# F7.net
KiCad netlist of a schematic drawn in EAGLE
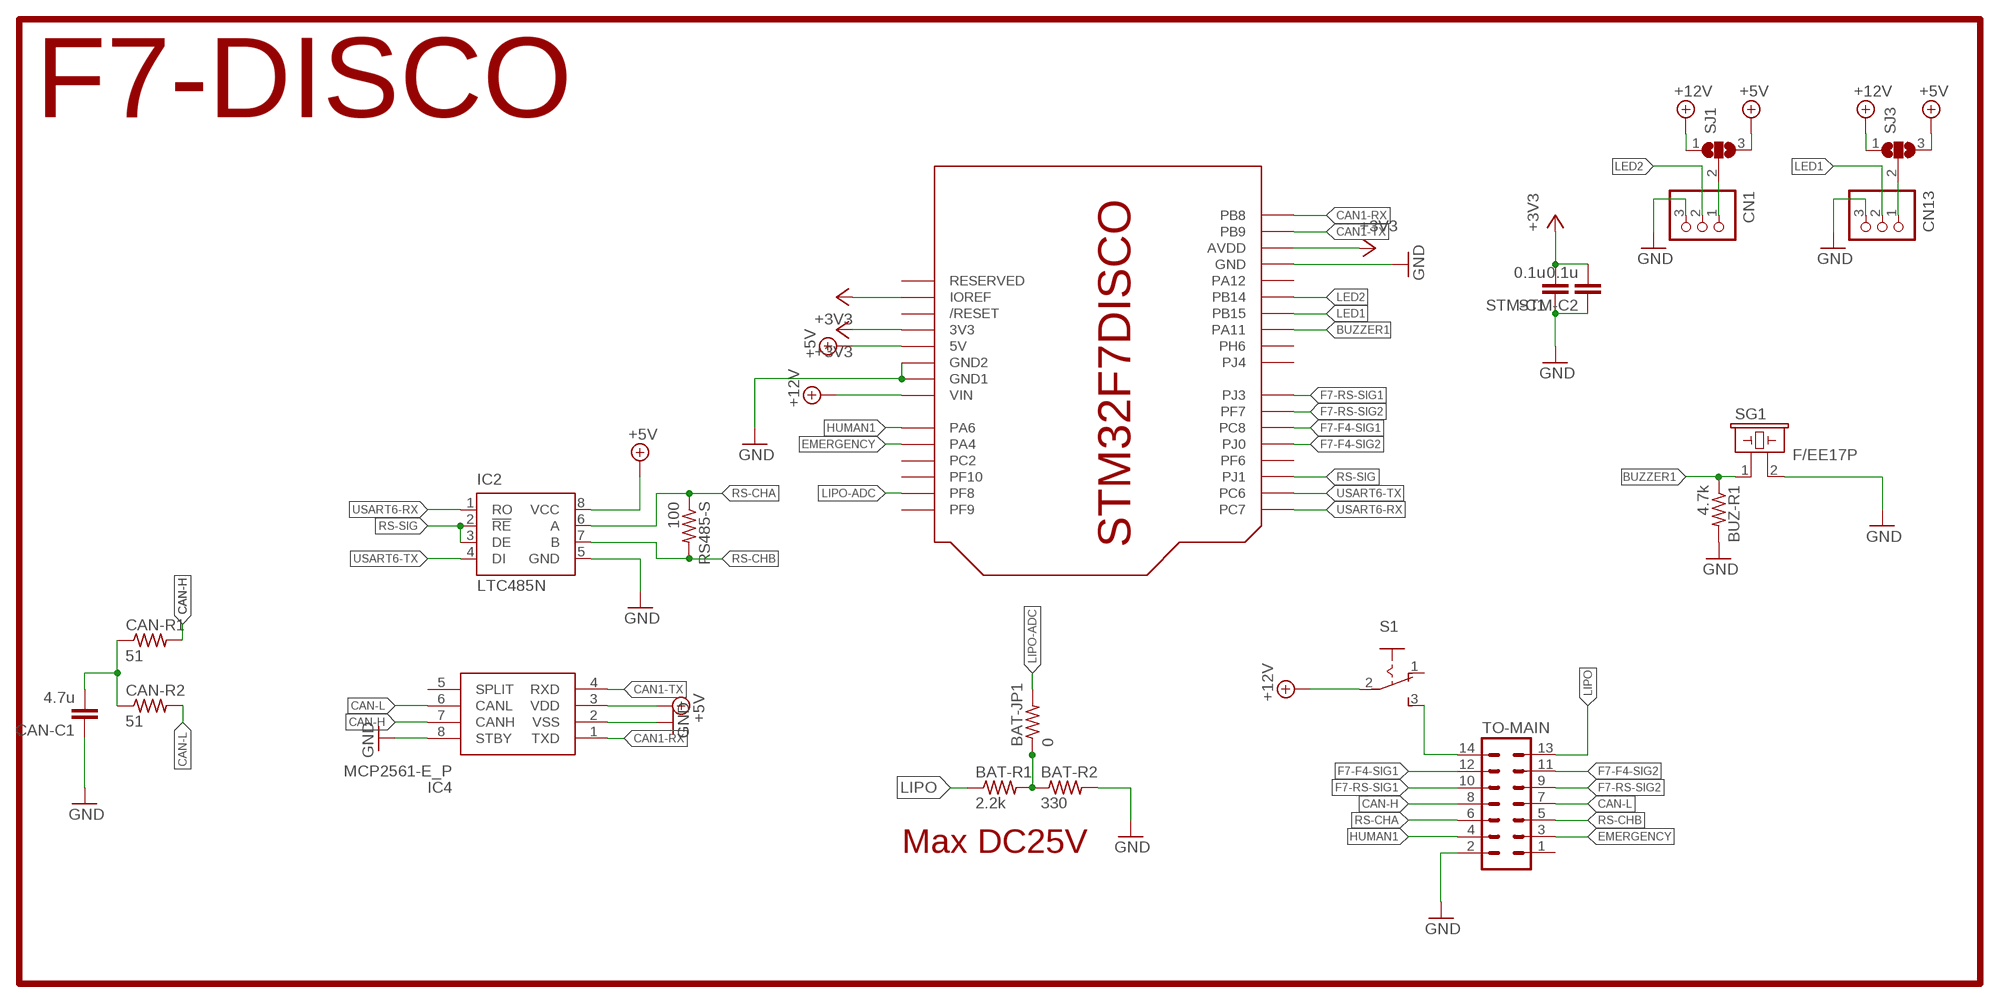
[diagram p0: schematic, sheet 1]

(export (version "E")
  (design (tool "Eeschema 10.0.6"))
  (components
    (comp (ref "BAT-JP1")
      (value "0")
      (footprint "eagle-import:R0805")
      (libsource (lib "eagle-import") (part "R-US_R0805"))
    )
    (comp (ref "BAT-R1")
      (value "2.2k")
      (footprint "eagle-import:R0805")
      (libsource (lib "eagle-import") (part "R-US_R0805"))
    )
    (comp (ref "BAT-R2")
      (value "330")
      (footprint "eagle-import:R0805")
      (libsource (lib "eagle-import") (part "R-US_R0805"))
    )
    (comp (ref "BUZ-R1")
      (value "4.7k")
      (footprint "eagle-import:R0805")
      (libsource (lib "eagle-import") (part "R-US_R0805"))
    )
    (comp (ref "CAN-C1")
      (value "4.7u")
      (footprint "eagle-import:C0805")
      (libsource (lib "eagle-import") (part "C-EUC0805"))
    )
    (comp (ref "CAN-R1")
      (value "51")
      (footprint "eagle-import:R0805")
      (libsource (lib "eagle-import") (part "R-US_R0805"))
    )
    (comp (ref "CAN-R2")
      (value "51")
      (footprint "eagle-import:R0805")
      (libsource (lib "eagle-import") (part "R-US_R0805"))
    )
    (comp (ref "CN1")
      (value "B3P-VH")
      (footprint "eagle-import:B3P-VH")
      (libsource (lib "eagle-import") (part "B3P-VH"))
    )
    (comp (ref "CN13")
      (value "B3P-VH")
      (footprint "eagle-import:B3P-VH")
      (libsource (lib "eagle-import") (part "B3P-VH"))
    )
    (comp (ref "IC2")
      (value "LTC485N")
      (footprint "eagle-import:DIL08")
      (libsource (lib "eagle-import") (part "LTC485N"))
    )
    (comp (ref "IC4")
      (value "MCP2561-E_P")
      (footprint "eagle-import:DIP781W56P254L950H533Q8N")
      (fields
        (field (name "MANUFACTURER_PART_NUMBER") "MCP2561-E/P")
        (field (name "MOUSER_PART_NUMBER") "579-MCP2561-E/P")
        (field (name "RS_PART_NUMBER") "1652124")
      )
      (libsource (lib "eagle-import") (part "MCP2561-E_P"))
    )
    (comp (ref "RS485-S")
      (value "100")
      (footprint "eagle-import:R0805")
      (libsource (lib "eagle-import") (part "R-US_R0805"))
    )
    (comp (ref "S1")
      (value "255SB")
      (footprint "eagle-import:255SB")
      (libsource (lib "eagle-import") (part "255SB"))
    )
    (comp (ref "SG1")
      (value "F/EE17P")
      (footprint "eagle-import:F_EE17P")
      (libsource (lib "eagle-import") (part "F/EE17P"))
    )
    (comp (ref "SJ1")
      (value "SJ2WW")
      (footprint "eagle-import:SJ_2W")
      (libsource (lib "eagle-import") (part "SJ2WW"))
    )
    (comp (ref "SJ3")
      (value "SJ2WW")
      (footprint "eagle-import:SJ_2W")
      (libsource (lib "eagle-import") (part "SJ2WW"))
    )
    (comp (ref "STM-C1")
      (value "0.1u")
      (footprint "eagle-import:C0805")
      (libsource (lib "eagle-import") (part "C-EUC0805"))
    )
    (comp (ref "STM-C2")
      (value "0.1u")
      (footprint "eagle-import:C0805")
      (libsource (lib "eagle-import") (part "C-EUC0805"))
    )
    (comp (ref "TO-MAIN")
      (value "ML14")
      (footprint "eagle-import:ML14")
      (libsource (lib "eagle-import") (part "ML14"))
    )
    (comp (ref "U$1")
      (value "F7-DISCO-ARDUINO")
      (footprint "eagle-import:F7-DISCO-ARDUINO")
      (libsource (lib "eagle-import") (part "F7-DISCO-ARDUINO"))
    )
  )
  (nets
    (net (code "1") (name "+5V") (class "Default")
      (node (ref "IC2") (pin "8") (pinfunction "VCC_8") (pintype "input"))
      (node (ref "IC4") (pin "3") (pinfunction "VDD_3") (pintype "bidirectional"))
      (node (ref "SJ1") (pin "3") (pinfunction "3_3") (pintype "passive"))
      (node (ref "SJ3") (pin "3") (pinfunction "3_3") (pintype "passive"))
      (node (ref "U$1") (pin "5V") (pinfunction "5V_5V") (pintype "power_in"))
    )
    (net (code "2") (name "+9V") (class "Default")
      (node (ref "S1") (pin "2") (pinfunction "P_2") (pintype "passive"))
      (node (ref "SJ1") (pin "1") (pinfunction "1_1") (pintype "passive"))
      (node (ref "SJ3") (pin "1") (pinfunction "1_1") (pintype "passive"))
      (node (ref "U$1") (pin "VIN") (pinfunction "VIN_VIN") (pintype "power_in"))
    )
    (net (code "3") (name "BUZZER1") (class "Default")
      (node (ref "BUZ-R1") (pin "1") (pinfunction "1_1") (pintype "passive"))
      (node (ref "SG1") (pin "1") (pinfunction "1_1") (pintype "passive"))
      (node (ref "U$1") (pin "PA11") (pinfunction "PA11_PA11") (pintype "bidirectional"))
    )
    (net (code "4") (name "CAN-H") (class "Default")
      (node (ref "CAN-R1") (pin "2") (pinfunction "2_2") (pintype "passive"))
      (node (ref "IC4") (pin "7") (pinfunction "CANH_7") (pintype "bidirectional"))
      (node (ref "TO-MAIN") (pin "8") (pinfunction "8_8") (pintype "passive"))
    )
    (net (code "5") (name "CAN-L") (class "Default")
      (node (ref "CAN-R2") (pin "2") (pinfunction "2_2") (pintype "passive"))
      (node (ref "IC4") (pin "6") (pinfunction "CANL_6") (pintype "bidirectional"))
      (node (ref "TO-MAIN") (pin "7") (pinfunction "7_7") (pintype "passive"))
    )
    (net (code "6") (name "CAN1-RX") (class "Default")
      (node (ref "IC4") (pin "1") (pinfunction "TXD_1") (pintype "bidirectional"))
      (node (ref "U$1") (pin "PB8") (pinfunction "PB8_PB8") (pintype "bidirectional"))
    )
    (net (code "7") (name "CAN1-TX") (class "Default")
      (node (ref "IC4") (pin "4") (pinfunction "RXD_4") (pintype "bidirectional"))
      (node (ref "U$1") (pin "PB9") (pinfunction "PB9_PB9") (pintype "bidirectional"))
    )
    (net (code "8") (name "EMERGENCY") (class "Default")
      (node (ref "TO-MAIN") (pin "3") (pinfunction "3_3") (pintype "passive"))
      (node (ref "U$1") (pin "PA4") (pinfunction "PA4_PA4") (pintype "bidirectional"))
    )
    (net (code "9") (name "F7-F4-SIG1") (class "Default")
      (node (ref "TO-MAIN") (pin "12") (pinfunction "12_12") (pintype "passive"))
      (node (ref "U$1") (pin "PC8") (pinfunction "PC8_PC8") (pintype "bidirectional"))
    )
    (net (code "10") (name "F7-F4-SIG2") (class "Default")
      (node (ref "TO-MAIN") (pin "11") (pinfunction "11_11") (pintype "passive"))
      (node (ref "U$1") (pin "PJ0") (pinfunction "PJ0_PJ0") (pintype "bidirectional"))
    )
    (net (code "11") (name "F7-RS-SIG1") (class "Default")
      (node (ref "TO-MAIN") (pin "10") (pinfunction "10_10") (pintype "passive"))
      (node (ref "U$1") (pin "PJ3") (pinfunction "PJ3_PJ3") (pintype "bidirectional"))
    )
    (net (code "12") (name "F7-RS-SIG2") (class "Default")
      (node (ref "TO-MAIN") (pin "9") (pinfunction "9_9") (pintype "passive"))
      (node (ref "U$1") (pin "PF7") (pinfunction "PF7_PF7") (pintype "bidirectional"))
    )
    (net (code "13") (name "GND") (class "Default")
      (node (ref "BAT-R2") (pin "2") (pinfunction "2_2") (pintype "passive"))
      (node (ref "BUZ-R1") (pin "2") (pinfunction "2_2") (pintype "passive"))
      (node (ref "CAN-C1") (pin "1") (pinfunction "1_1") (pintype "passive"))
      (node (ref "CN1") (pin "3") (pinfunction "3_3") (pintype "passive"))
      (node (ref "CN13") (pin "3") (pinfunction "3_3") (pintype "passive"))
      (node (ref "IC2") (pin "5") (pinfunction "GND_5") (pintype "input"))
      (node (ref "IC4") (pin "2") (pinfunction "VSS_2") (pintype "bidirectional"))
      (node (ref "IC4") (pin "8") (pinfunction "STBY_8") (pintype "bidirectional"))
      (node (ref "SG1") (pin "2") (pinfunction "2_2") (pintype "passive"))
      (node (ref "STM-C1") (pin "1") (pinfunction "1_1") (pintype "passive"))
      (node (ref "STM-C2") (pin "1") (pinfunction "1_1") (pintype "passive"))
      (node (ref "TO-MAIN") (pin "2") (pinfunction "2_2") (pintype "passive"))
      (node (ref "U$1") (pin "GND1") (pinfunction "GND_GND1") (pintype "power_in"))
      (node (ref "U$1") (pin "GND@1") (pinfunction "GND1_GND@1") (pintype "power_in"))
      (node (ref "U$1") (pin "GND@2") (pinfunction "GND2_GND@2") (pintype "power_in"))
    )
    (net (code "14") (name "HUMAN1") (class "Default")
      (node (ref "TO-MAIN") (pin "4") (pinfunction "4_4") (pintype "passive"))
      (node (ref "U$1") (pin "PA6") (pinfunction "PA6_PA6") (pintype "bidirectional"))
    )
    (net (code "15") (name "LED1") (class "Default")
      (node (ref "CN13") (pin "2") (pinfunction "2_2") (pintype "passive"))
      (node (ref "U$1") (pin "PB15") (pinfunction "PB15_PB15") (pintype "bidirectional"))
    )
    (net (code "16") (name "LED2") (class "Default")
      (node (ref "CN1") (pin "2") (pinfunction "2_2") (pintype "passive"))
      (node (ref "U$1") (pin "PB14") (pinfunction "PB14_PB14") (pintype "bidirectional"))
    )
    (net (code "17") (name "LIPO") (class "Default")
      (node (ref "BAT-R1") (pin "1") (pinfunction "1_1") (pintype "passive"))
      (node (ref "TO-MAIN") (pin "13") (pinfunction "13_13") (pintype "passive"))
    )
    (net (code "18") (name "LIPO-ADC") (class "Default")
      (node (ref "BAT-JP1") (pin "2") (pinfunction "2_2") (pintype "passive"))
      (node (ref "U$1") (pin "PF8") (pinfunction "PF8_PF8") (pintype "bidirectional"))
    )
    (net (code "19") (name "Net-(BAT-JP1-Pad1)") (class "Default")
      (node (ref "BAT-JP1") (pin "1") (pinfunction "1_1") (pintype "passive"))
      (node (ref "BAT-R1") (pin "2") (pinfunction "2_2") (pintype "passive"))
      (node (ref "BAT-R2") (pin "1") (pinfunction "1_1") (pintype "passive"))
    )
    (net (code "20") (name "Net-(CAN-C1-Pad2)") (class "Default")
      (node (ref "CAN-C1") (pin "2") (pinfunction "2_2") (pintype "passive"))
      (node (ref "CAN-R1") (pin "1") (pinfunction "1_1") (pintype "passive"))
      (node (ref "CAN-R2") (pin "1") (pinfunction "1_1") (pintype "passive"))
    )
    (net (code "21") (name "Net-(CN1-Pad1)") (class "Default")
      (node (ref "CN1") (pin "1") (pinfunction "1_1") (pintype "passive"))
      (node (ref "SJ1") (pin "2") (pinfunction "2_2") (pintype "passive"))
    )
    (net (code "22") (name "Net-(CN13-Pad1)") (class "Default")
      (node (ref "CN13") (pin "1") (pinfunction "1_1") (pintype "passive"))
      (node (ref "SJ3") (pin "2") (pinfunction "2_2") (pintype "passive"))
    )
    (net (code "23") (name "Net-(S1-S)") (class "Default")
      (node (ref "S1") (pin "3") (pinfunction "S_3") (pintype "passive"))
      (node (ref "TO-MAIN") (pin "14") (pinfunction "14_14") (pintype "passive"))
    )
    (net (code "24") (name "RS-CHA") (class "Default")
      (node (ref "IC2") (pin "6") (pinfunction "A_6") (pintype "bidirectional"))
      (node (ref "RS485-S") (pin "1") (pinfunction "1_1") (pintype "passive"))
      (node (ref "TO-MAIN") (pin "6") (pinfunction "6_6") (pintype "passive"))
    )
    (net (code "25") (name "RS-CHB") (class "Default")
      (node (ref "IC2") (pin "7") (pinfunction "B_7") (pintype "bidirectional"))
      (node (ref "RS485-S") (pin "2") (pinfunction "2_2") (pintype "passive"))
      (node (ref "TO-MAIN") (pin "5") (pinfunction "5_5") (pintype "passive"))
    )
    (net (code "26") (name "RS-SIG") (class "Default")
      (node (ref "IC2") (pin "2") (pinfunction "~{RE}_2") (pintype "input"))
      (node (ref "IC2") (pin "3") (pinfunction "DE_3") (pintype "input"))
      (node (ref "U$1") (pin "PJ1") (pinfunction "PJ1_PJ1") (pintype "bidirectional"))
    )
    (net (code "27") (name "USART6-RX") (class "Default")
      (node (ref "IC2") (pin "1") (pinfunction "RO_1") (pintype "output"))
      (node (ref "U$1") (pin "PC7") (pinfunction "PC7_PC7") (pintype "bidirectional"))
    )
    (net (code "28") (name "USART6-TX") (class "Default")
      (node (ref "IC2") (pin "4") (pinfunction "DI_4") (pintype "input"))
      (node (ref "U$1") (pin "PC6") (pinfunction "PC6_PC6") (pintype "bidirectional"))
    )
    (net (code "29") (name "VCC") (class "Default")
      (node (ref "STM-C1") (pin "2") (pinfunction "2_2") (pintype "passive"))
      (node (ref "STM-C2") (pin "2") (pinfunction "2_2") (pintype "passive"))
      (node (ref "U$1") (pin "3V") (pinfunction "3V3_3V") (pintype "power_in"))
      (node (ref "U$1") (pin "AVDD") (pinfunction "AVDD_AVDD") (pintype "bidirectional"))
      (node (ref "U$1") (pin "IOREF") (pinfunction "IOREF_IOREF") (pintype "output"))
    )
    (net (code "30") (name "unconnected-(IC4-SPLIT-Pad5)") (class "Default")
      (node (ref "IC4") (pin "5") (pinfunction "SPLIT_5") (pintype "bidirectional"))
    )
    (net (code "31") (name "unconnected-(S1-O-Pad1)") (class "Default")
      (node (ref "S1") (pin "1") (pinfunction "O_1") (pintype "passive"))
    )
    (net (code "32") (name "unconnected-(TO-MAIN-Pad1)") (class "Default")
      (node (ref "TO-MAIN") (pin "1") (pinfunction "1_1") (pintype "passive"))
    )
    (net (code "33") (name "unconnected-(U$1-PadPA12)") (class "Default")
      (node (ref "U$1") (pin "PA12") (pinfunction "PA12_PA12") (pintype "bidirectional"))
    )
    (net (code "34") (name "unconnected-(U$1-PadPC2)") (class "Default")
      (node (ref "U$1") (pin "PC2") (pinfunction "PC2_PC2") (pintype "bidirectional"))
    )
    (net (code "35") (name "unconnected-(U$1-PadPF6)") (class "Default")
      (node (ref "U$1") (pin "PF6") (pinfunction "PF6_PF6") (pintype "bidirectional"))
    )
    (net (code "36") (name "unconnected-(U$1-PadPF9)") (class "Default")
      (node (ref "U$1") (pin "PF9") (pinfunction "PF9_PF9") (pintype "bidirectional"))
    )
    (net (code "37") (name "unconnected-(U$1-PadPF10)") (class "Default")
      (node (ref "U$1") (pin "PF10") (pinfunction "PF10_PF10") (pintype "bidirectional"))
    )
    (net (code "38") (name "unconnected-(U$1-PadPH6)") (class "Default")
      (node (ref "U$1") (pin "PH6") (pinfunction "PH6_PH6") (pintype "bidirectional"))
    )
    (net (code "39") (name "unconnected-(U$1-PadPJ4)") (class "Default")
      (node (ref "U$1") (pin "PJ4") (pinfunction "PJ4_PJ4") (pintype "bidirectional"))
    )
    (net (code "40") (name "unconnected-(U$1-PadRESERVED)") (class "Default")
      (node (ref "U$1") (pin "RESERVED") (pinfunction "RESERVED_RESERVED") (pintype "bidirectional"))
    )
    (net (code "41") (name "unconnected-(U$1-{slash}RESET-PadRESET)") (class "Default")
      (node (ref "U$1") (pin "RESET") (pinfunction "/RESET_RESET") (pintype "bidirectional"))
    )
  )
)
